# myLEDBlinker.net
KiCad netlist of a schematic drawn in Altium Designer
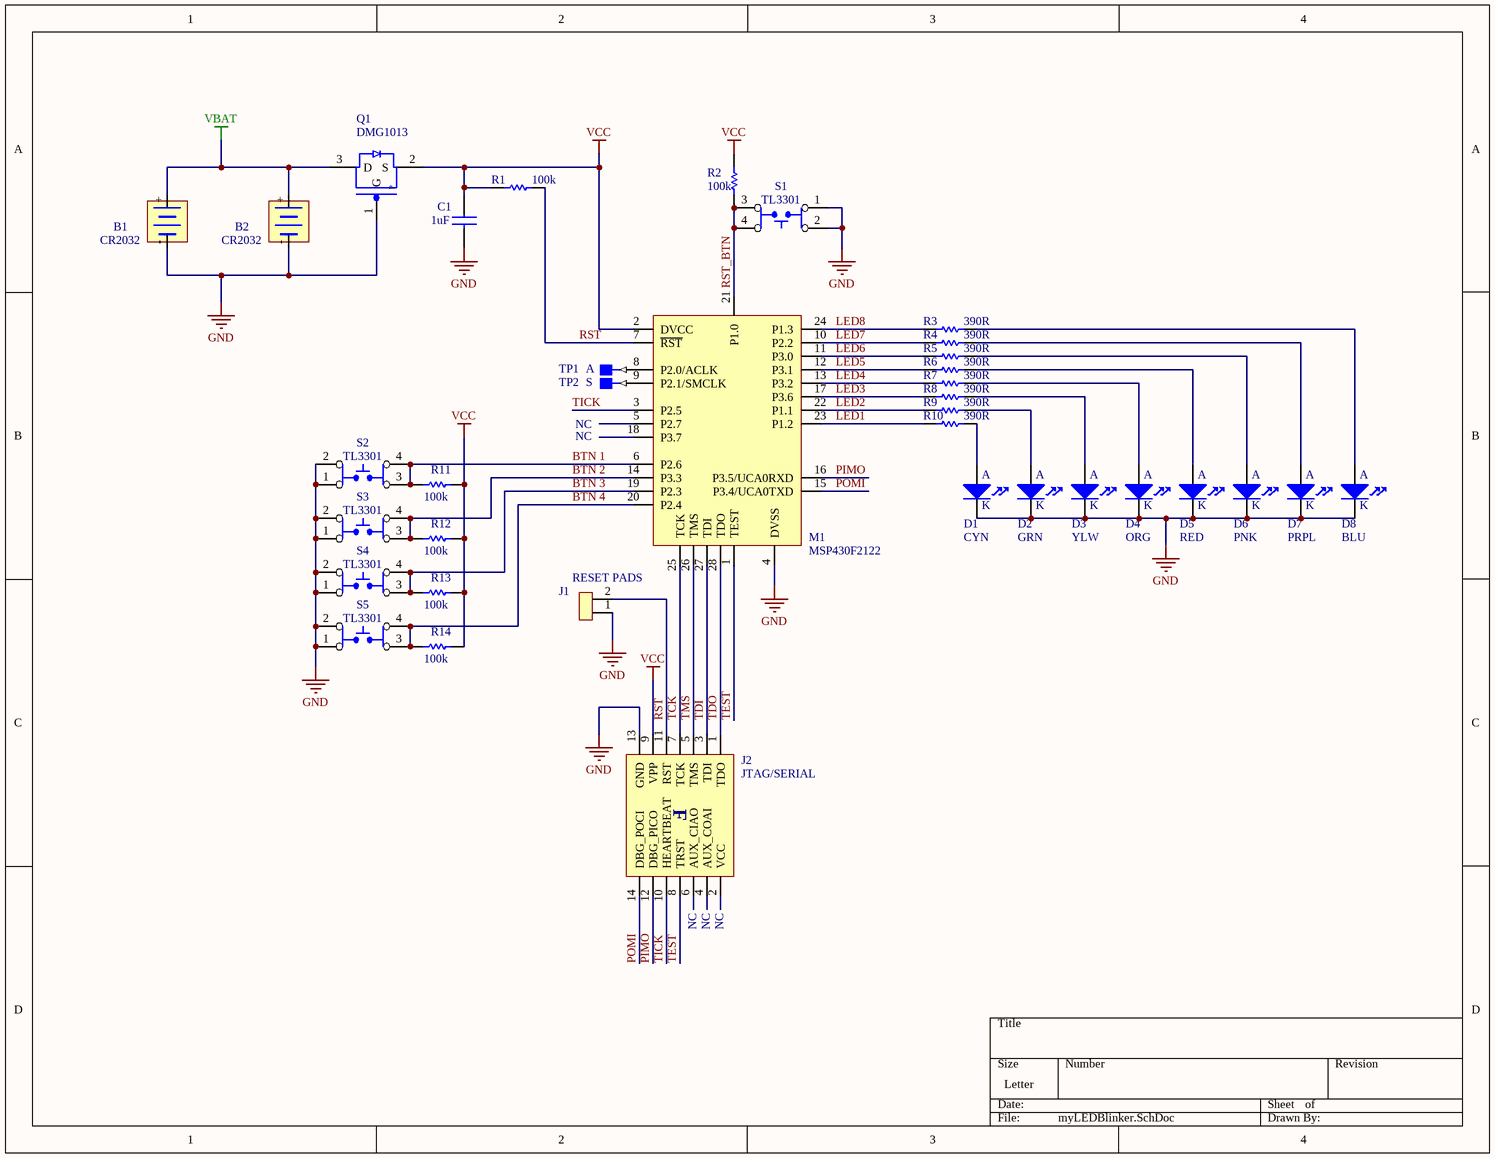
[diagram p0: myLEDBlinker.SchDoc]

(export (version "E")
  (design (tool "Eeschema 10.0.6"))
  (components
    (comp (ref "B1")
      (value "CR2032")
      (footprint "CONN BATTERY HOLDER CR2032")
      (description "3V Coincell Battery")
      (fields
        (field (name "3. MANUFACTURER PART NUMBER") "BK-912")
        (field (name "4. DIGI-KEY PART NUMBER") "BK-912-ND")
        (field (name "7. MODIFIED BY") "JRL")
      )
      (libsource (lib "Altium Example Master Schematic Library") (part "CONN BATTERY HOLDER CR2032"))
    )
    (comp (ref "B2")
      (value "CR2032")
      (footprint "CONN BATTERY HOLDER CR2032")
      (description "3V Coincell Battery")
      (fields
        (field (name "3. MANUFACTURER PART NUMBER") "BK-912")
        (field (name "4. DIGI-KEY PART NUMBER") "BK-912-ND")
        (field (name "7. MODIFIED BY") "JRL")
      )
      (libsource (lib "Altium Example Master Schematic Library") (part "CONN BATTERY HOLDER CR2032"))
    )
    (comp (ref "C1")
      (value "1uF")
      (footprint "0603")
      (fields
        (field (name "4. DIGI-KEY PART NUMBER") "587-1251-2-ND")
        (field (name "3. MANUFACTURER PART NUMBER") "EMK107BJ105KA-T")
        (field (name "7. MODIFIED BY") "BJW")
      )
      (libsource (lib "Altium Example Master Schematic Library") (part "CAPACITOR NON-POLARIZED"))
    )
    (comp (ref "D1")
      (value "CYN")
      (footprint "PLCC-2 AK")
      (description "CYAN")
      (fields (field (name "7. MODIFIED BY") "BJW"))
      (libsource (lib "Altium Example Master Schematic Library") (part "LED AK"))
    )
    (comp (ref "D2")
      (value "GRN")
      (footprint "PLCC-2 AK")
      (description "GREEN")
      (fields
        (field (name "3. MANUFACTURER PART NUMBER") "AA3528CGSK")
        (field (name "4. DIGI-KEY PART NUMBER") "754-1528-2-ND")
        (field (name "7. MODIFIED BY") "BJW")
      )
      (libsource (lib "Altium Example Master Schematic Library") (part "LED AK"))
    )
    (comp (ref "D3")
      (value "YLW")
      (footprint "PLCC-2 AK")
      (description "YELLOW")
      (fields
        (field (name "3. MANUFACTURER PART NUMBER") "AA3528SYCK")
        (field (name "4. DIGI-KEY PART NUMBER") "754-2077-2-ND")
        (field (name "7. MODIFIED BY") "BJW")
      )
      (libsource (lib "Altium Example Master Schematic Library") (part "LED AK"))
    )
    (comp (ref "D4")
      (value "ORG")
      (footprint "PLCC-2 AK")
      (description "ORANGE")
      (fields
        (field (name "3. MANUFACTURER PART NUMBER") "AA3528SESK")
        (field (name "4. DIGI-KEY PART NUMBER") "754-1536-2-ND")
        (field (name "7. MODIFIED BY") "BJW")
      )
      (libsource (lib "Altium Example Master Schematic Library") (part "LED AK"))
    )
    (comp (ref "D5")
      (value "RED")
      (footprint "PLCC-2 AK")
      (fields
        (field (name "3. MANUFACTURER PART NUMBER") "AA3528SURSK")
        (field (name "4. DIGI-KEY PART NUMBER") "754-1537-2-ND")
        (field (name "7. MODIFIED BY") "BJW")
      )
      (libsource (lib "Altium Example Master Schematic Library") (part "LED AK"))
    )
    (comp (ref "D6")
      (value "PNK")
      (footprint "PLCC-2 AK")
      (description "PINK")
      (fields
        (field (name "3. MANUFACTURER PART NUMBER") "AA3528VRVCS/A")
        (field (name "4. DIGI-KEY PART NUMBER") "754-1534-2-ND")
        (field (name "7. MODIFIED BY") "BJW")
      )
      (libsource (lib "Altium Example Master Schematic Library") (part "LED AK"))
    )
    (comp (ref "D7")
      (value "PRPL")
      (footprint "PLCC-2 AK")
      (description "PURPLE")
      (fields
        (field (name "3. MANUFACTURER PART NUMBER") "AA3528VRVFS/A")
        (field (name "4. DIGI-KEY PART NUMBER") "754-1535-2-ND")
        (field (name "7. MODIFIED BY") "BJW")
      )
      (libsource (lib "Altium Example Master Schematic Library") (part "LED AK"))
    )
    (comp (ref "D8")
      (value "BLU")
      (footprint "PLCC-2 AK")
      (description "BLUE")
      (fields
        (field (name "3. MANUFACTURER PART NUMBER") "AA3528QBS/D")
        (field (name "4. DIGI-KEY PART NUMBER") "754-1533-2-ND")
        (field (name "7. MODIFIED BY") "BJW")
      )
      (libsource (lib "Altium Example Master Schematic Library") (part "LED AK"))
    )
    (comp (ref "J1")
      (value "RESET PADS")
      (footprint "HDR1X2")
      (fields (field (name "7. MODIFIED BY") "*"))
      (libsource (lib "Altium Example Master Schematic Library") (part "CONN SIP 2"))
    )
    (comp (ref "J2")
      (value "JTAG/SERIAL")
      (footprint "CONN 14POS 7X2 SMT FEMALE SMALL")
      (fields
        (field (name "3. MANUFACTURER PART NUMBER") "20021321-00014T4LF")
        (field (name "4. DIGI-KEY PART NUMBER") "609-3771-ND")
        (field (name "5. INTERNAL PART NUMBER") "100254")
        (field (name "7. MODIFIED BY") "BJW")
      )
      (libsource (lib "Altium Example Master Schematic Library") (part "CONN JTAG/SERIAL FEMALE"))
    )
    (comp (ref "M1")
      (value "MSP430F2122")
      (footprint "TSSOP28")
      (fields
        (field (name "3. MANUFACTURER PART NUMBER") "MSP430F2122TPWR")
        (field (name "4. DIGI-KEY PART NUMBER") "296-23365-ND")
        (field (name "7. MODIFIED BY") "BJW")
      )
      (libsource (lib "Altium Example Master Schematic Library") (part "MCU MSP430F2122 TSSOP28"))
    )
    (comp (ref "Q1")
      (value "DMG1013")
      (footprint "SC-70-3")
      (fields
        (field (name "3. MANUFACTURER PART NUMBER") "DMG1013UW-7")
        (field (name "4. DIGI-KEY PART NUMBER") "DMG1013UW-7DITR-ND")
        (field (name "7. MODIFIED BY") "BJW")
      )
      (libsource (lib "Altium Example Master Schematic Library") (part "TRANS PMOS 1G 2S 3D"))
    )
    (comp (ref "R1")
      (value "100k")
      (footprint "0603")
      (fields
        (field (name "4. DIGI-KEY PART NUMBER") "311-100KHRTR-ND")
        (field (name "3. MANUFACTURER PART NUMBER") "RC0603FR-07100KL")
        (field (name "7. MODIFIED BY") "BJW")
      )
      (libsource (lib "Altium Example Master Schematic Library") (part "RESISTOR"))
    )
    (comp (ref "R2")
      (value "100k")
      (footprint "0603")
      (fields
        (field (name "4. DIGI-KEY PART NUMBER") "311-100KHRTR-ND")
        (field (name "3. MANUFACTURER PART NUMBER") "RC0603FR-07100KL")
        (field (name "7. MODIFIED BY") "BJW")
      )
      (libsource (lib "Altium Example Master Schematic Library") (part "RESISTOR"))
    )
    (comp (ref "R3")
      (value "390R")
      (footprint "0603")
      (fields
        (field (name "4. DIGI-KEY PART NUMBER") "311-390HRTR-ND")
        (field (name "3. MANUFACTURER PART NUMBER") "RC0603FR-07390RL")
        (field (name "7. MODIFIED BY") "BJW")
      )
      (libsource (lib "Altium Example Master Schematic Library") (part "RESISTOR"))
    )
    (comp (ref "R4")
      (value "390R")
      (footprint "0603")
      (fields
        (field (name "4. DIGI-KEY PART NUMBER") "311-390HRTR-ND")
        (field (name "3. MANUFACTURER PART NUMBER") "RC0603FR-07390RL")
        (field (name "7. MODIFIED BY") "BJW")
      )
      (libsource (lib "Altium Example Master Schematic Library") (part "RESISTOR"))
    )
    (comp (ref "R5")
      (value "390R")
      (footprint "0603")
      (fields
        (field (name "4. DIGI-KEY PART NUMBER") "311-390HRTR-ND")
        (field (name "3. MANUFACTURER PART NUMBER") "RC0603FR-07390RL")
        (field (name "7. MODIFIED BY") "BJW")
      )
      (libsource (lib "Altium Example Master Schematic Library") (part "RESISTOR"))
    )
    (comp (ref "R6")
      (value "390R")
      (footprint "0603")
      (fields
        (field (name "4. DIGI-KEY PART NUMBER") "311-390HRTR-ND")
        (field (name "3. MANUFACTURER PART NUMBER") "RC0603FR-07390RL")
        (field (name "7. MODIFIED BY") "BJW")
      )
      (libsource (lib "Altium Example Master Schematic Library") (part "RESISTOR"))
    )
    (comp (ref "R7")
      (value "390R")
      (footprint "0603")
      (fields
        (field (name "4. DIGI-KEY PART NUMBER") "311-390HRTR-ND")
        (field (name "3. MANUFACTURER PART NUMBER") "RC0603FR-07390RL")
        (field (name "7. MODIFIED BY") "BJW")
      )
      (libsource (lib "Altium Example Master Schematic Library") (part "RESISTOR"))
    )
    (comp (ref "R8")
      (value "390R")
      (footprint "0603")
      (fields
        (field (name "4. DIGI-KEY PART NUMBER") "311-390HRTR-ND")
        (field (name "3. MANUFACTURER PART NUMBER") "RC0603FR-07390RL")
        (field (name "7. MODIFIED BY") "BJW")
      )
      (libsource (lib "Altium Example Master Schematic Library") (part "RESISTOR"))
    )
    (comp (ref "R9")
      (value "390R")
      (footprint "0603")
      (fields
        (field (name "4. DIGI-KEY PART NUMBER") "311-390HRTR-ND")
        (field (name "3. MANUFACTURER PART NUMBER") "RC0603FR-07390RL")
        (field (name "7. MODIFIED BY") "BJW")
      )
      (libsource (lib "Altium Example Master Schematic Library") (part "RESISTOR"))
    )
    (comp (ref "R10")
      (value "390R")
      (footprint "0603")
      (fields
        (field (name "4. DIGI-KEY PART NUMBER") "311-390HRTR-ND")
        (field (name "3. MANUFACTURER PART NUMBER") "RC0603FR-07390RL")
        (field (name "7. MODIFIED BY") "BJW")
      )
      (libsource (lib "Altium Example Master Schematic Library") (part "RESISTOR"))
    )
    (comp (ref "R11")
      (value "100k")
      (footprint "0603")
      (fields
        (field (name "4. DIGI-KEY PART NUMBER") "311-100KHRTR-ND")
        (field (name "3. MANUFACTURER PART NUMBER") "RC0603FR-07100KL")
        (field (name "7. MODIFIED BY") "BJW")
      )
      (libsource (lib "Altium Example Master Schematic Library") (part "RESISTOR"))
    )
    (comp (ref "R12")
      (value "100k")
      (footprint "0603")
      (fields
        (field (name "4. DIGI-KEY PART NUMBER") "311-100KHRTR-ND")
        (field (name "3. MANUFACTURER PART NUMBER") "RC0603FR-07100KL")
        (field (name "7. MODIFIED BY") "BJW")
      )
      (libsource (lib "Altium Example Master Schematic Library") (part "RESISTOR"))
    )
    (comp (ref "R13")
      (value "100k")
      (footprint "0603")
      (fields
        (field (name "4. DIGI-KEY PART NUMBER") "311-100KHRTR-ND")
        (field (name "3. MANUFACTURER PART NUMBER") "RC0603FR-07100KL")
        (field (name "7. MODIFIED BY") "BJW")
      )
      (libsource (lib "Altium Example Master Schematic Library") (part "RESISTOR"))
    )
    (comp (ref "R14")
      (value "100k")
      (footprint "0603")
      (fields
        (field (name "4. DIGI-KEY PART NUMBER") "311-100KHRTR-ND")
        (field (name "3. MANUFACTURER PART NUMBER") "RC0603FR-07100KL")
        (field (name "7. MODIFIED BY") "BJW")
      )
      (libsource (lib "Altium Example Master Schematic Library") (part "RESISTOR"))
    )
    (comp (ref "S1")
      (value "TL3301")
      (footprint "SWITCH TACT SMT TL3301")
      (description "SPST TACT SWITCH")
      (fields
        (field (name "3. MANUFACTURER PART NUMBER") "TL3301AF160QJ")
        (field (name "4. DIGI-KEY PART NUMBER") "EG4374TR-ND")
        (field (name "7. MODIFIED BY") "BJW")
      )
      (libsource (lib "Altium Example Master Schematic Library") (part "SWITCH SPST TL3301 JLEAD"))
    )
    (comp (ref "S2")
      (value "TL3301")
      (footprint "SWITCH TACT SMT TL3301")
      (description "SPST TACT SWITCH")
      (fields
        (field (name "3. MANUFACTURER PART NUMBER") "TL3301AF160QJ")
        (field (name "4. DIGI-KEY PART NUMBER") "EG4374TR-ND")
        (field (name "7. MODIFIED BY") "BJW")
      )
      (libsource (lib "Altium Example Master Schematic Library") (part "SWITCH SPST TL3301 JLEAD"))
    )
    (comp (ref "S3")
      (value "TL3301")
      (footprint "SWITCH TACT SMT TL3301")
      (description "SPST TACT SWITCH")
      (fields
        (field (name "3. MANUFACTURER PART NUMBER") "TL3301AF160QJ")
        (field (name "4. DIGI-KEY PART NUMBER") "EG4374TR-ND")
        (field (name "7. MODIFIED BY") "BJW")
      )
      (libsource (lib "Altium Example Master Schematic Library") (part "SWITCH SPST TL3301 JLEAD"))
    )
    (comp (ref "S4")
      (value "TL3301")
      (footprint "SWITCH TACT SMT TL3301")
      (description "SPST TACT SWITCH")
      (fields
        (field (name "3. MANUFACTURER PART NUMBER") "TL3301AF160QJ")
        (field (name "4. DIGI-KEY PART NUMBER") "EG4374TR-ND")
        (field (name "7. MODIFIED BY") "BJW")
      )
      (libsource (lib "Altium Example Master Schematic Library") (part "SWITCH SPST TL3301 JLEAD"))
    )
    (comp (ref "S5")
      (value "TL3301")
      (footprint "SWITCH TACT SMT TL3301")
      (description "SPST TACT SWITCH")
      (fields
        (field (name "3. MANUFACTURER PART NUMBER") "TL3301AF160QJ")
        (field (name "4. DIGI-KEY PART NUMBER") "EG4374TR-ND")
        (field (name "7. MODIFIED BY") "BJW")
      )
      (libsource (lib "Altium Example Master Schematic Library") (part "SWITCH SPST TL3301 JLEAD"))
    )
    (comp (ref "TP1")
      (value "A")
      (footprint "TEST POINT SMT")
      (fields (field (name "7. MODIFIED BY") "JRL"))
      (libsource (lib "Altium Example Master Schematic Library") (part "TEST POINT SMT"))
    )
    (comp (ref "TP2")
      (value "S")
      (footprint "TEST POINT SMT")
      (fields (field (name "7. MODIFIED BY") "JRL"))
      (libsource (lib "Altium Example Master Schematic Library") (part "TEST POINT SMT"))
    )
  )
  (nets
    (net (code "1") (name "/BTN 1") (class "Default")
      (node (ref "M1") (pin "6") (pinfunction "P2.6_6") (pintype "passive"))
      (node (ref "R11") (pin "1") (pinfunction "1_1") (pintype "passive"))
      (node (ref "S2") (pin "3") (pinfunction "Y1_3") (pintype "passive"))
      (node (ref "S2") (pin "4") (pinfunction "Y2_4") (pintype "passive"))
    )
    (net (code "2") (name "/BTN 2") (class "Default")
      (node (ref "M1") (pin "14") (pinfunction "P3.3_14") (pintype "passive"))
      (node (ref "R12") (pin "1") (pinfunction "1_1") (pintype "passive"))
      (node (ref "S3") (pin "3") (pinfunction "Y1_3") (pintype "passive"))
      (node (ref "S3") (pin "4") (pinfunction "Y2_4") (pintype "passive"))
    )
    (net (code "3") (name "/BTN 3") (class "Default")
      (node (ref "M1") (pin "19") (pinfunction "P2.3_19") (pintype "passive"))
      (node (ref "R13") (pin "1") (pinfunction "1_1") (pintype "passive"))
      (node (ref "S4") (pin "3") (pinfunction "Y1_3") (pintype "passive"))
      (node (ref "S4") (pin "4") (pinfunction "Y2_4") (pintype "passive"))
    )
    (net (code "4") (name "/BTN 4") (class "Default")
      (node (ref "M1") (pin "20") (pinfunction "P2.4_20") (pintype "passive"))
      (node (ref "R14") (pin "1") (pinfunction "1_1") (pintype "passive"))
      (node (ref "S5") (pin "3") (pinfunction "Y1_3") (pintype "passive"))
      (node (ref "S5") (pin "4") (pinfunction "Y2_4") (pintype "passive"))
    )
    (net (code "5") (name "/LED1") (class "Default")
      (node (ref "M1") (pin "23") (pinfunction "P1.2_23") (pintype "passive"))
      (node (ref "R10") (pin "1") (pinfunction "1_1") (pintype "passive"))
    )
    (net (code "6") (name "/LED2") (class "Default")
      (node (ref "M1") (pin "22") (pinfunction "P1.1_22") (pintype "passive"))
      (node (ref "R9") (pin "1") (pinfunction "1_1") (pintype "passive"))
    )
    (net (code "7") (name "/LED3") (class "Default")
      (node (ref "M1") (pin "17") (pinfunction "P3.6_17") (pintype "passive"))
      (node (ref "R8") (pin "1") (pinfunction "1_1") (pintype "passive"))
    )
    (net (code "8") (name "/LED4") (class "Default")
      (node (ref "M1") (pin "13") (pinfunction "P3.2_13") (pintype "passive"))
      (node (ref "R7") (pin "1") (pinfunction "1_1") (pintype "passive"))
    )
    (net (code "9") (name "/LED5") (class "Default")
      (node (ref "M1") (pin "12") (pinfunction "P3.1_12") (pintype "passive"))
      (node (ref "R6") (pin "1") (pinfunction "1_1") (pintype "passive"))
    )
    (net (code "10") (name "/LED6") (class "Default")
      (node (ref "M1") (pin "11") (pinfunction "P3.0_11") (pintype "passive"))
      (node (ref "R5") (pin "1") (pinfunction "1_1") (pintype "passive"))
    )
    (net (code "11") (name "/LED7") (class "Default")
      (node (ref "M1") (pin "10") (pinfunction "P2.2_10") (pintype "passive"))
      (node (ref "R4") (pin "1") (pinfunction "1_1") (pintype "passive"))
    )
    (net (code "12") (name "/LED8") (class "Default")
      (node (ref "M1") (pin "24") (pinfunction "P1.3_24") (pintype "passive"))
      (node (ref "R3") (pin "1") (pinfunction "1_1") (pintype "passive"))
    )
    (net (code "13") (name "/PIMO") (class "Default")
      (node (ref "J2") (pin "12") (pinfunction "DBG_PICO_12") (pintype "passive"))
      (node (ref "M1") (pin "16") (pinfunction "P3.5/UCA0RXD_16") (pintype "passive"))
    )
    (net (code "14") (name "/POMI") (class "Default")
      (node (ref "J2") (pin "14") (pinfunction "DBG_POCI_14") (pintype "passive"))
      (node (ref "M1") (pin "15") (pinfunction "P3.4/UCA0TXD_15") (pintype "passive"))
    )
    (net (code "15") (name "/RST") (class "Default")
      (node (ref "J1") (pin "2") (pintype "passive"))
      (node (ref "J2") (pin "11") (pinfunction "RST_11") (pintype "passive"))
      (node (ref "M1") (pin "7") (pinfunction "~{RST}_7") (pintype "passive"))
      (node (ref "R1") (pin "2") (pinfunction "2_2") (pintype "passive"))
    )
    (net (code "16") (name "/RST_BTN") (class "Default")
      (node (ref "M1") (pin "21") (pinfunction "P1.0_21") (pintype "passive"))
      (node (ref "R2") (pin "1") (pinfunction "1_1") (pintype "passive"))
      (node (ref "S1") (pin "3") (pinfunction "Y1_3") (pintype "passive"))
      (node (ref "S1") (pin "4") (pinfunction "Y2_4") (pintype "passive"))
    )
    (net (code "17") (name "/TCK") (class "Default")
      (node (ref "J2") (pin "7") (pinfunction "TCK_7") (pintype "passive"))
      (node (ref "M1") (pin "25") (pinfunction "TCK_25") (pintype "passive"))
    )
    (net (code "18") (name "/TDI") (class "Default")
      (node (ref "J2") (pin "3") (pinfunction "TDI_3") (pintype "passive"))
      (node (ref "M1") (pin "27") (pinfunction "TDI_27") (pintype "passive"))
    )
    (net (code "19") (name "/TDO") (class "Default")
      (node (ref "J2") (pin "1") (pinfunction "TDO_1") (pintype "passive"))
      (node (ref "M1") (pin "28") (pinfunction "TDO_28") (pintype "passive"))
    )
    (net (code "20") (name "/TEST") (class "Default")
      (node (ref "J2") (pin "8") (pinfunction "TRST_8") (pintype "passive"))
      (node (ref "M1") (pin "1") (pinfunction "TEST_1") (pintype "passive"))
    )
    (net (code "21") (name "/TICK") (class "Default")
      (node (ref "J2") (pin "10") (pinfunction "HEARTBEAT_10") (pintype "passive"))
      (node (ref "M1") (pin "3") (pinfunction "P2.5_3") (pintype "passive"))
    )
    (net (code "22") (name "/TMS") (class "Default")
      (node (ref "J2") (pin "5") (pinfunction "TMS_5") (pintype "passive"))
      (node (ref "M1") (pin "26") (pinfunction "TMS_26") (pintype "passive"))
    )
    (net (code "23") (name "GND") (class "Default")
      (node (ref "B1") (pin "-") (pintype "passive"))
      (node (ref "B2") (pin "-") (pintype "passive"))
      (node (ref "C1") (pin "2") (pinfunction "2_2") (pintype "passive"))
      (node (ref "D1") (pin "K") (pinfunction "K_K") (pintype "passive"))
      (node (ref "D2") (pin "K") (pinfunction "K_K") (pintype "passive"))
      (node (ref "D3") (pin "K") (pinfunction "K_K") (pintype "passive"))
      (node (ref "D4") (pin "K") (pinfunction "K_K") (pintype "passive"))
      (node (ref "D5") (pin "K") (pinfunction "K_K") (pintype "passive"))
      (node (ref "D6") (pin "K") (pinfunction "K_K") (pintype "passive"))
      (node (ref "D7") (pin "K") (pinfunction "K_K") (pintype "passive"))
      (node (ref "D8") (pin "K") (pinfunction "K_K") (pintype "passive"))
      (node (ref "J1") (pin "1") (pintype "passive"))
      (node (ref "J2") (pin "13") (pinfunction "GND_13") (pintype "passive"))
      (node (ref "M1") (pin "4") (pinfunction "DVSS_4") (pintype "passive"))
      (node (ref "Q1") (pin "1") (pinfunction "G_1") (pintype "passive"))
      (node (ref "S1") (pin "1") (pinfunction "X1_1") (pintype "passive"))
      (node (ref "S1") (pin "2") (pinfunction "X2_2") (pintype "passive"))
      (node (ref "S2") (pin "1") (pinfunction "X1_1") (pintype "passive"))
      (node (ref "S2") (pin "2") (pinfunction "X2_2") (pintype "passive"))
      (node (ref "S3") (pin "1") (pinfunction "X1_1") (pintype "passive"))
      (node (ref "S3") (pin "2") (pinfunction "X2_2") (pintype "passive"))
      (node (ref "S4") (pin "1") (pinfunction "X1_1") (pintype "passive"))
      (node (ref "S4") (pin "2") (pinfunction "X2_2") (pintype "passive"))
      (node (ref "S5") (pin "1") (pinfunction "X1_1") (pintype "passive"))
      (node (ref "S5") (pin "2") (pinfunction "X2_2") (pintype "passive"))
    )
    (net (code "24") (name "Net-(D1-PadA)") (class "Default")
      (node (ref "D1") (pin "A") (pinfunction "A_A") (pintype "passive"))
      (node (ref "R10") (pin "2") (pinfunction "2_2") (pintype "passive"))
    )
    (net (code "25") (name "Net-(D2-PadA)") (class "Default")
      (node (ref "D2") (pin "A") (pinfunction "A_A") (pintype "passive"))
      (node (ref "R9") (pin "2") (pinfunction "2_2") (pintype "passive"))
    )
    (net (code "26") (name "Net-(D3-PadA)") (class "Default")
      (node (ref "D3") (pin "A") (pinfunction "A_A") (pintype "passive"))
      (node (ref "R8") (pin "2") (pinfunction "2_2") (pintype "passive"))
    )
    (net (code "27") (name "Net-(D4-PadA)") (class "Default")
      (node (ref "D4") (pin "A") (pinfunction "A_A") (pintype "passive"))
      (node (ref "R7") (pin "2") (pinfunction "2_2") (pintype "passive"))
    )
    (net (code "28") (name "Net-(D5-PadA)") (class "Default")
      (node (ref "D5") (pin "A") (pinfunction "A_A") (pintype "passive"))
      (node (ref "R6") (pin "2") (pinfunction "2_2") (pintype "passive"))
    )
    (net (code "29") (name "Net-(D6-PadA)") (class "Default")
      (node (ref "D6") (pin "A") (pinfunction "A_A") (pintype "passive"))
      (node (ref "R5") (pin "2") (pinfunction "2_2") (pintype "passive"))
    )
    (net (code "30") (name "Net-(D7-PadA)") (class "Default")
      (node (ref "D7") (pin "A") (pinfunction "A_A") (pintype "passive"))
      (node (ref "R4") (pin "2") (pinfunction "2_2") (pintype "passive"))
    )
    (net (code "31") (name "Net-(D8-PadA)") (class "Default")
      (node (ref "D8") (pin "A") (pinfunction "A_A") (pintype "passive"))
      (node (ref "R3") (pin "2") (pinfunction "2_2") (pintype "passive"))
    )
    (net (code "32") (name "Net-(M1-P2.0{slash}ACLK)") (class "Default")
      (node (ref "M1") (pin "8") (pinfunction "P2.0/ACLK_8") (pintype "passive"))
      (node (ref "TP1") (pin "1") (pinfunction "1_1") (pintype "input"))
    )
    (net (code "33") (name "Net-(M1-P2.1{slash}SMCLK)") (class "Default")
      (node (ref "M1") (pin "9") (pinfunction "P2.1/SMCLK_9") (pintype "passive"))
      (node (ref "TP2") (pin "1") (pinfunction "1_1") (pintype "input"))
    )
    (net (code "34") (name "VBAT") (class "Default")
      (node (ref "B1") (pin "+") (pintype "passive"))
      (node (ref "B2") (pin "+") (pintype "passive"))
      (node (ref "Q1") (pin "3") (pinfunction "D_3") (pintype "passive"))
    )
    (net (code "35") (name "VCC") (class "Default")
      (node (ref "C1") (pin "1") (pinfunction "1_1") (pintype "passive"))
      (node (ref "J2") (pin "9") (pinfunction "VPP_9") (pintype "passive"))
      (node (ref "M1") (pin "2") (pinfunction "DVCC_2") (pintype "passive"))
      (node (ref "Q1") (pin "2") (pinfunction "S_2") (pintype "passive"))
      (node (ref "R1") (pin "1") (pinfunction "1_1") (pintype "passive"))
      (node (ref "R11") (pin "2") (pinfunction "2_2") (pintype "passive"))
      (node (ref "R12") (pin "2") (pinfunction "2_2") (pintype "passive"))
      (node (ref "R13") (pin "2") (pinfunction "2_2") (pintype "passive"))
      (node (ref "R14") (pin "2") (pinfunction "2_2") (pintype "passive"))
      (node (ref "R2") (pin "2") (pinfunction "2_2") (pintype "passive"))
    )
    (net (code "36") (name "unconnected-(J2-AUX_CIAO-Pad6)") (class "Default")
      (node (ref "J2") (pin "6") (pinfunction "AUX_CIAO_6") (pintype "passive"))
    )
    (net (code "37") (name "unconnected-(J2-AUX_COAI-Pad4)") (class "Default")
      (node (ref "J2") (pin "4") (pinfunction "AUX_COAI_4") (pintype "passive"))
    )
    (net (code "38") (name "unconnected-(J2-VCC-Pad2)") (class "Default")
      (node (ref "J2") (pin "2") (pinfunction "VCC_2") (pintype "passive"))
    )
    (net (code "39") (name "unconnected-(M1-P2.7-Pad5)") (class "Default")
      (node (ref "M1") (pin "5") (pinfunction "P2.7_5") (pintype "passive"))
    )
    (net (code "40") (name "unconnected-(M1-P3.7-Pad18)") (class "Default")
      (node (ref "M1") (pin "18") (pinfunction "P3.7_18") (pintype "passive"))
    )
  )
)
